# 2te8x24V_DC_In_4_v03.net
KiCad netlist of a schematic drawn in EAGLE
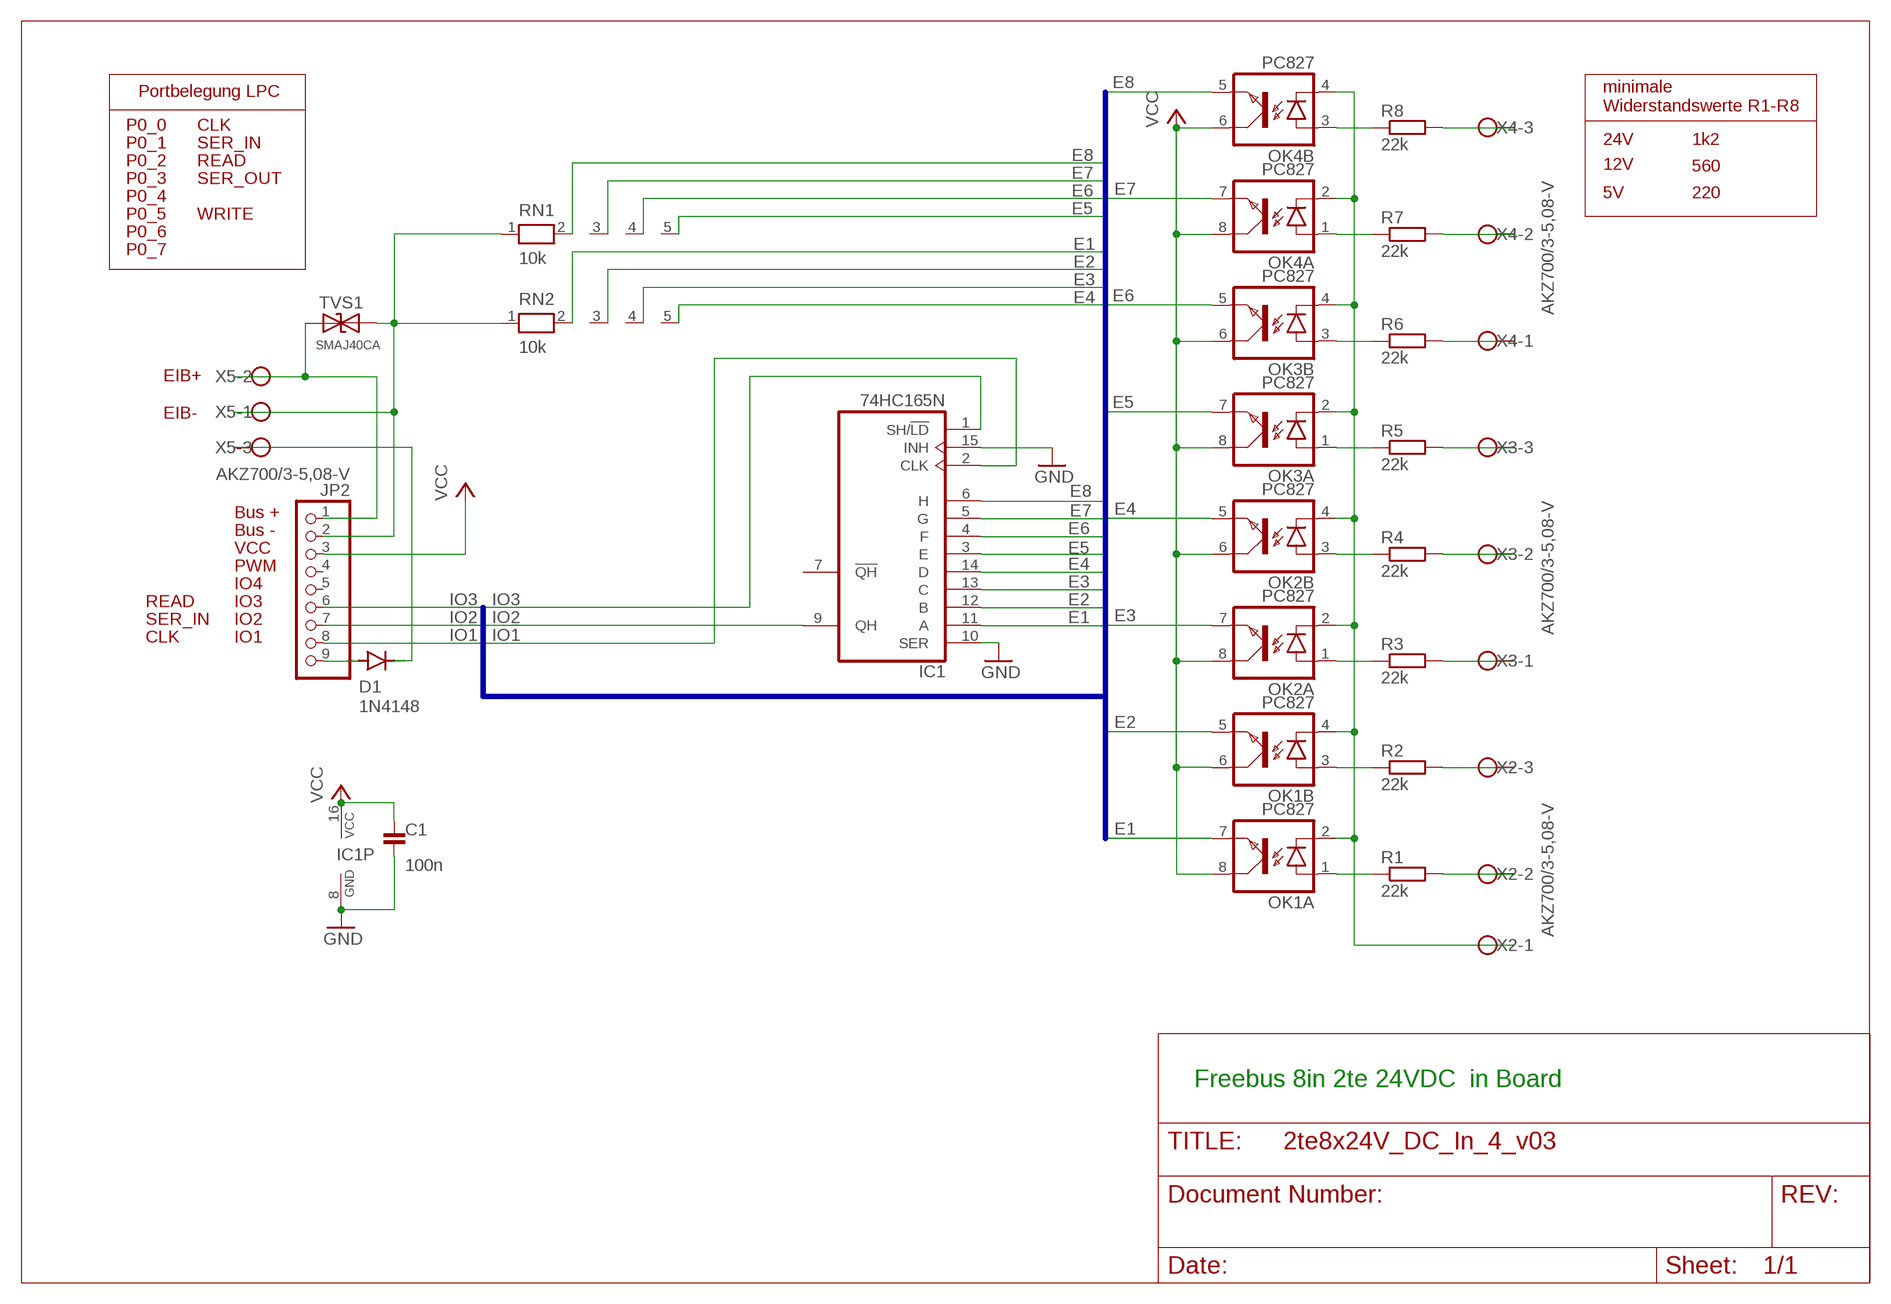
[diagram p0: schematic, sheet 1]

(export (version "E")
  (design (tool "Eeschema 10.0.6"))
  (components
    (comp (ref "C1")
      (value "100n")
      (footprint "eagle-import:C025-024X044")
      (libsource (lib "eagle-import") (part "C-EU025-024X044"))
    )
    (comp (ref "D1")
      (value "1N4148")
      (footprint "eagle-import:DO35-7")
      (libsource (lib "eagle-import") (part "1N4148DO35-7"))
    )
    (comp (ref "IC1")
      (value "74HC165N")
      (footprint "eagle-import:DIL16")
      (libsource (lib "eagle-import") (part "74165NHC"))
    )
    (comp (ref "JP2")
      (value "PINHD-1X9")
      (footprint "eagle-import:1X09")
      (libsource (lib "eagle-import") (part "PINHD-1X9"))
    )
    (comp (ref "OK1")
      (value "PC827")
      (footprint "eagle-import:DIL08")
      (libsource (lib "eagle-import") (part "PC827"))
    )
    (comp (ref "OK2")
      (value "PC827")
      (footprint "eagle-import:DIL08")
      (libsource (lib "eagle-import") (part "PC827"))
    )
    (comp (ref "OK3")
      (value "PC827")
      (footprint "eagle-import:DIL08")
      (libsource (lib "eagle-import") (part "PC827"))
    )
    (comp (ref "OK4")
      (value "PC827")
      (footprint "eagle-import:DIL08")
      (libsource (lib "eagle-import") (part "PC827"))
    )
    (comp (ref "R1")
      (value "22k")
      (footprint "eagle-import:0207_10")
      (libsource (lib "eagle-import") (part "R-EU_0207/10"))
    )
    (comp (ref "R2")
      (value "22k")
      (footprint "eagle-import:0207_10")
      (libsource (lib "eagle-import") (part "R-EU_0207/10"))
    )
    (comp (ref "R3")
      (value "22k")
      (footprint "eagle-import:0207_10")
      (libsource (lib "eagle-import") (part "R-EU_0207/10"))
    )
    (comp (ref "R4")
      (value "22k")
      (footprint "eagle-import:0207_10")
      (libsource (lib "eagle-import") (part "R-EU_0207/10"))
    )
    (comp (ref "R5")
      (value "22k")
      (footprint "eagle-import:0207_10")
      (libsource (lib "eagle-import") (part "R-EU_0207/10"))
    )
    (comp (ref "R6")
      (value "22k")
      (footprint "eagle-import:0207_10")
      (libsource (lib "eagle-import") (part "R-EU_0207/10"))
    )
    (comp (ref "R7")
      (value "22k")
      (footprint "eagle-import:0207_10")
      (libsource (lib "eagle-import") (part "R-EU_0207/10"))
    )
    (comp (ref "R8")
      (value "22k")
      (footprint "eagle-import:0207_10")
      (libsource (lib "eagle-import") (part "R-EU_0207/10"))
    )
    (comp (ref "RN1")
      (value "10k")
      (footprint "eagle-import:RN-5")
      (libsource (lib "eagle-import") (part "RN04"))
    )
    (comp (ref "RN2")
      (value "10k")
      (footprint "eagle-import:RN-5")
      (libsource (lib "eagle-import") (part "RN04"))
    )
    (comp (ref "TVS1")
      (value "SMAJ40CA")
      (footprint "eagle-import:DO-214AC(SMA)_BI")
      (libsource (lib "eagle-import") (part "SMAJCA40"))
    )
    (comp (ref "X2")
      (value "AKZ700/3-5,08-V")
      (footprint "eagle-import:AKZ700_3-5,08-V")
      (libsource (lib "eagle-import") (part "AKZ700/3-5,08-V"))
    )
    (comp (ref "X3")
      (value "AKZ700/3-5,08-V")
      (footprint "eagle-import:AKZ700_3-5,08-V")
      (libsource (lib "eagle-import") (part "AKZ700/3-5,08-V"))
    )
    (comp (ref "X4")
      (value "AKZ700/3-5,08-V")
      (footprint "eagle-import:AKZ700_3-5,08-V")
      (libsource (lib "eagle-import") (part "AKZ700/3-5,08-V"))
    )
    (comp (ref "X5")
      (value "AKZ700/3-5,08-V")
      (footprint "eagle-import:AKZ700_3-5,08-V")
      (libsource (lib "eagle-import") (part "AKZ700/3-5,08-V"))
    )
  )
  (nets
    (net (code "1") (name "/E1") (class "Default")
      (node (ref "IC1") (pin "11") (pinfunction "A_11") (pintype "input"))
      (node (ref "OK1") (pin "7") (pinfunction "EMIT_7") (pintype "passive"))
      (node (ref "RN2") (pin "2") (pinfunction "2_2") (pintype "passive"))
    )
    (net (code "2") (name "/E2") (class "Default")
      (node (ref "IC1") (pin "12") (pinfunction "B_12") (pintype "input"))
      (node (ref "OK1") (pin "5") (pinfunction "EMIT_5") (pintype "passive"))
      (node (ref "RN2") (pin "3") (pinfunction "3_3") (pintype "passive"))
    )
    (net (code "3") (name "/E3") (class "Default")
      (node (ref "IC1") (pin "13") (pinfunction "C_13") (pintype "input"))
      (node (ref "OK2") (pin "7") (pinfunction "EMIT_7") (pintype "passive"))
      (node (ref "RN2") (pin "4") (pinfunction "4_4") (pintype "passive"))
    )
    (net (code "4") (name "/E4") (class "Default")
      (node (ref "IC1") (pin "14") (pinfunction "D_14") (pintype "input"))
      (node (ref "OK2") (pin "5") (pinfunction "EMIT_5") (pintype "passive"))
      (node (ref "RN2") (pin "5") (pinfunction "5_5") (pintype "passive"))
    )
    (net (code "5") (name "/E5") (class "Default")
      (node (ref "IC1") (pin "3") (pinfunction "E_3") (pintype "input"))
      (node (ref "OK3") (pin "7") (pinfunction "EMIT_7") (pintype "passive"))
      (node (ref "RN1") (pin "5") (pinfunction "5_5") (pintype "passive"))
    )
    (net (code "6") (name "/E6") (class "Default")
      (node (ref "IC1") (pin "4") (pinfunction "F_4") (pintype "input"))
      (node (ref "OK3") (pin "5") (pinfunction "EMIT_5") (pintype "passive"))
      (node (ref "RN1") (pin "4") (pinfunction "4_4") (pintype "passive"))
    )
    (net (code "7") (name "/E7") (class "Default")
      (node (ref "IC1") (pin "5") (pinfunction "G_5") (pintype "input"))
      (node (ref "OK4") (pin "7") (pinfunction "EMIT_7") (pintype "passive"))
      (node (ref "RN1") (pin "3") (pinfunction "3_3") (pintype "passive"))
    )
    (net (code "8") (name "/E8") (class "Default")
      (node (ref "IC1") (pin "6") (pinfunction "H_6") (pintype "input"))
      (node (ref "OK4") (pin "5") (pinfunction "EMIT_5") (pintype "passive"))
      (node (ref "RN1") (pin "2") (pinfunction "2_2") (pintype "passive"))
    )
    (net (code "9") (name "/IO1") (class "Default")
      (node (ref "IC1") (pin "2") (pinfunction "CLK_2") (pintype "input"))
      (node (ref "JP2") (pin "8") (pinfunction "8_8") (pintype "passive"))
    )
    (net (code "10") (name "/IO2") (class "Default")
      (node (ref "IC1") (pin "9") (pinfunction "QH_9") (pintype "output"))
      (node (ref "JP2") (pin "7") (pinfunction "7_7") (pintype "passive"))
    )
    (net (code "11") (name "/IO3") (class "Default")
      (node (ref "IC1") (pin "1") (pinfunction "SH/~{LD}_1") (pintype "input"))
      (node (ref "JP2") (pin "6") (pinfunction "6_6") (pintype "passive"))
    )
    (net (code "12") (name "GND") (class "Default")
      (node (ref "C1") (pin "2") (pinfunction "2_2") (pintype "passive"))
      (node (ref "IC1") (pin "10") (pinfunction "SER_10") (pintype "input"))
      (node (ref "IC1") (pin "15") (pinfunction "INH_15") (pintype "input"))
      (node (ref "IC1") (pin "8") (pinfunction "GND_8") (pintype "power_in"))
      (node (ref "JP2") (pin "2") (pinfunction "2_2") (pintype "passive"))
      (node (ref "RN1") (pin "1") (pinfunction "1_1") (pintype "passive"))
      (node (ref "RN2") (pin "1") (pinfunction "1_1") (pintype "passive"))
      (node (ref "TVS1") (pin "1") (pinfunction "A1_1") (pintype "passive"))
      (node (ref "X5") (pin "1") (pinfunction "KL_1") (pintype "passive"))
    )
    (net (code "13") (name "Net-(D1-PadA)") (class "Default")
      (node (ref "D1") (pin "A") (pinfunction "A_A") (pintype "passive"))
      (node (ref "JP2") (pin "9") (pinfunction "9_9") (pintype "passive"))
    )
    (net (code "14") (name "Net-(OK1A-A)") (class "Default")
      (node (ref "OK1") (pin "1") (pinfunction "A_1") (pintype "passive"))
      (node (ref "R1") (pin "1") (pinfunction "1_1") (pintype "passive"))
    )
    (net (code "15") (name "Net-(OK1A-C)") (class "Default")
      (node (ref "OK1") (pin "2") (pinfunction "C_2") (pintype "passive"))
      (node (ref "OK1") (pin "4") (pinfunction "C_4") (pintype "passive"))
      (node (ref "OK2") (pin "2") (pinfunction "C_2") (pintype "passive"))
      (node (ref "OK2") (pin "4") (pinfunction "C_4") (pintype "passive"))
      (node (ref "OK3") (pin "2") (pinfunction "C_2") (pintype "passive"))
      (node (ref "OK3") (pin "4") (pinfunction "C_4") (pintype "passive"))
      (node (ref "OK4") (pin "2") (pinfunction "C_2") (pintype "passive"))
      (node (ref "OK4") (pin "4") (pinfunction "C_4") (pintype "passive"))
      (node (ref "X2") (pin "1") (pinfunction "KL_1") (pintype "passive"))
    )
    (net (code "16") (name "Net-(OK1B-A)") (class "Default")
      (node (ref "OK1") (pin "3") (pinfunction "A_3") (pintype "passive"))
      (node (ref "R2") (pin "1") (pinfunction "1_1") (pintype "passive"))
    )
    (net (code "17") (name "Net-(OK2A-A)") (class "Default")
      (node (ref "OK2") (pin "1") (pinfunction "A_1") (pintype "passive"))
      (node (ref "R3") (pin "1") (pinfunction "1_1") (pintype "passive"))
    )
    (net (code "18") (name "Net-(OK2B-A)") (class "Default")
      (node (ref "OK2") (pin "3") (pinfunction "A_3") (pintype "passive"))
      (node (ref "R4") (pin "1") (pinfunction "1_1") (pintype "passive"))
    )
    (net (code "19") (name "Net-(OK3A-A)") (class "Default")
      (node (ref "OK3") (pin "1") (pinfunction "A_1") (pintype "passive"))
      (node (ref "R5") (pin "1") (pinfunction "1_1") (pintype "passive"))
    )
    (net (code "20") (name "Net-(OK3B-A)") (class "Default")
      (node (ref "OK3") (pin "3") (pinfunction "A_3") (pintype "passive"))
      (node (ref "R6") (pin "1") (pinfunction "1_1") (pintype "passive"))
    )
    (net (code "21") (name "Net-(OK4A-A)") (class "Default")
      (node (ref "OK4") (pin "1") (pinfunction "A_1") (pintype "passive"))
      (node (ref "R7") (pin "1") (pinfunction "1_1") (pintype "passive"))
    )
    (net (code "22") (name "Net-(OK4B-A)") (class "Default")
      (node (ref "OK4") (pin "3") (pinfunction "A_3") (pintype "passive"))
      (node (ref "R8") (pin "1") (pinfunction "1_1") (pintype "passive"))
    )
    (net (code "23") (name "Net-(TVS1-A2)") (class "Default")
      (node (ref "JP2") (pin "1") (pinfunction "1_1") (pintype "passive"))
      (node (ref "TVS1") (pin "2") (pinfunction "A2_2") (pintype "passive"))
      (node (ref "X5") (pin "2") (pinfunction "KL_2") (pintype "passive"))
    )
    (net (code "24") (name "Net-(X2B-KL)") (class "Default")
      (node (ref "R1") (pin "2") (pinfunction "2_2") (pintype "passive"))
      (node (ref "X2") (pin "2") (pinfunction "KL_2") (pintype "passive"))
    )
    (net (code "25") (name "Net-(X2C-KL)") (class "Default")
      (node (ref "R2") (pin "2") (pinfunction "2_2") (pintype "passive"))
      (node (ref "X2") (pin "3") (pinfunction "KL_3") (pintype "passive"))
    )
    (net (code "26") (name "Net-(X3A-KL)") (class "Default")
      (node (ref "R3") (pin "2") (pinfunction "2_2") (pintype "passive"))
      (node (ref "X3") (pin "1") (pinfunction "KL_1") (pintype "passive"))
    )
    (net (code "27") (name "Net-(X3B-KL)") (class "Default")
      (node (ref "R4") (pin "2") (pinfunction "2_2") (pintype "passive"))
      (node (ref "X3") (pin "2") (pinfunction "KL_2") (pintype "passive"))
    )
    (net (code "28") (name "Net-(X3C-KL)") (class "Default")
      (node (ref "R5") (pin "2") (pinfunction "2_2") (pintype "passive"))
      (node (ref "X3") (pin "3") (pinfunction "KL_3") (pintype "passive"))
    )
    (net (code "29") (name "Net-(X4A-KL)") (class "Default")
      (node (ref "R6") (pin "2") (pinfunction "2_2") (pintype "passive"))
      (node (ref "X4") (pin "1") (pinfunction "KL_1") (pintype "passive"))
    )
    (net (code "30") (name "Net-(X4B-KL)") (class "Default")
      (node (ref "R7") (pin "2") (pinfunction "2_2") (pintype "passive"))
      (node (ref "X4") (pin "2") (pinfunction "KL_2") (pintype "passive"))
    )
    (net (code "31") (name "Net-(X4C-KL)") (class "Default")
      (node (ref "R8") (pin "2") (pinfunction "2_2") (pintype "passive"))
      (node (ref "X4") (pin "3") (pinfunction "KL_3") (pintype "passive"))
    )
    (net (code "32") (name "Net-(X5C-KL)") (class "Default")
      (node (ref "D1") (pin "C") (pinfunction "C_C") (pintype "passive"))
      (node (ref "X5") (pin "3") (pinfunction "KL_3") (pintype "passive"))
    )
    (net (code "33") (name "VCC") (class "Default")
      (node (ref "C1") (pin "1") (pinfunction "1_1") (pintype "passive"))
      (node (ref "IC1") (pin "16") (pinfunction "VCC_16") (pintype "power_in"))
      (node (ref "JP2") (pin "3") (pinfunction "3_3") (pintype "passive"))
      (node (ref "OK1") (pin "6") (pinfunction "COL_6") (pintype "passive"))
      (node (ref "OK1") (pin "8") (pinfunction "COL_8") (pintype "passive"))
      (node (ref "OK2") (pin "6") (pinfunction "COL_6") (pintype "passive"))
      (node (ref "OK2") (pin "8") (pinfunction "COL_8") (pintype "passive"))
      (node (ref "OK3") (pin "6") (pinfunction "COL_6") (pintype "passive"))
      (node (ref "OK3") (pin "8") (pinfunction "COL_8") (pintype "passive"))
      (node (ref "OK4") (pin "6") (pinfunction "COL_6") (pintype "passive"))
      (node (ref "OK4") (pin "8") (pinfunction "COL_8") (pintype "passive"))
    )
    (net (code "34") (name "unconnected-(IC1A-~{QH}-Pad7)") (class "Default")
      (node (ref "IC1") (pin "7") (pinfunction "~{QH}_7") (pintype "output"))
    )
    (net (code "35") (name "unconnected-(JP2-Pad4)") (class "Default")
      (node (ref "JP2") (pin "4") (pinfunction "4_4") (pintype "passive"))
    )
    (net (code "36") (name "unconnected-(JP2-Pad5)") (class "Default")
      (node (ref "JP2") (pin "5") (pinfunction "5_5") (pintype "passive"))
    )
  )
)
